# neuroskyStm.net
KiCad netlist of a schematic drawn in EAGLE
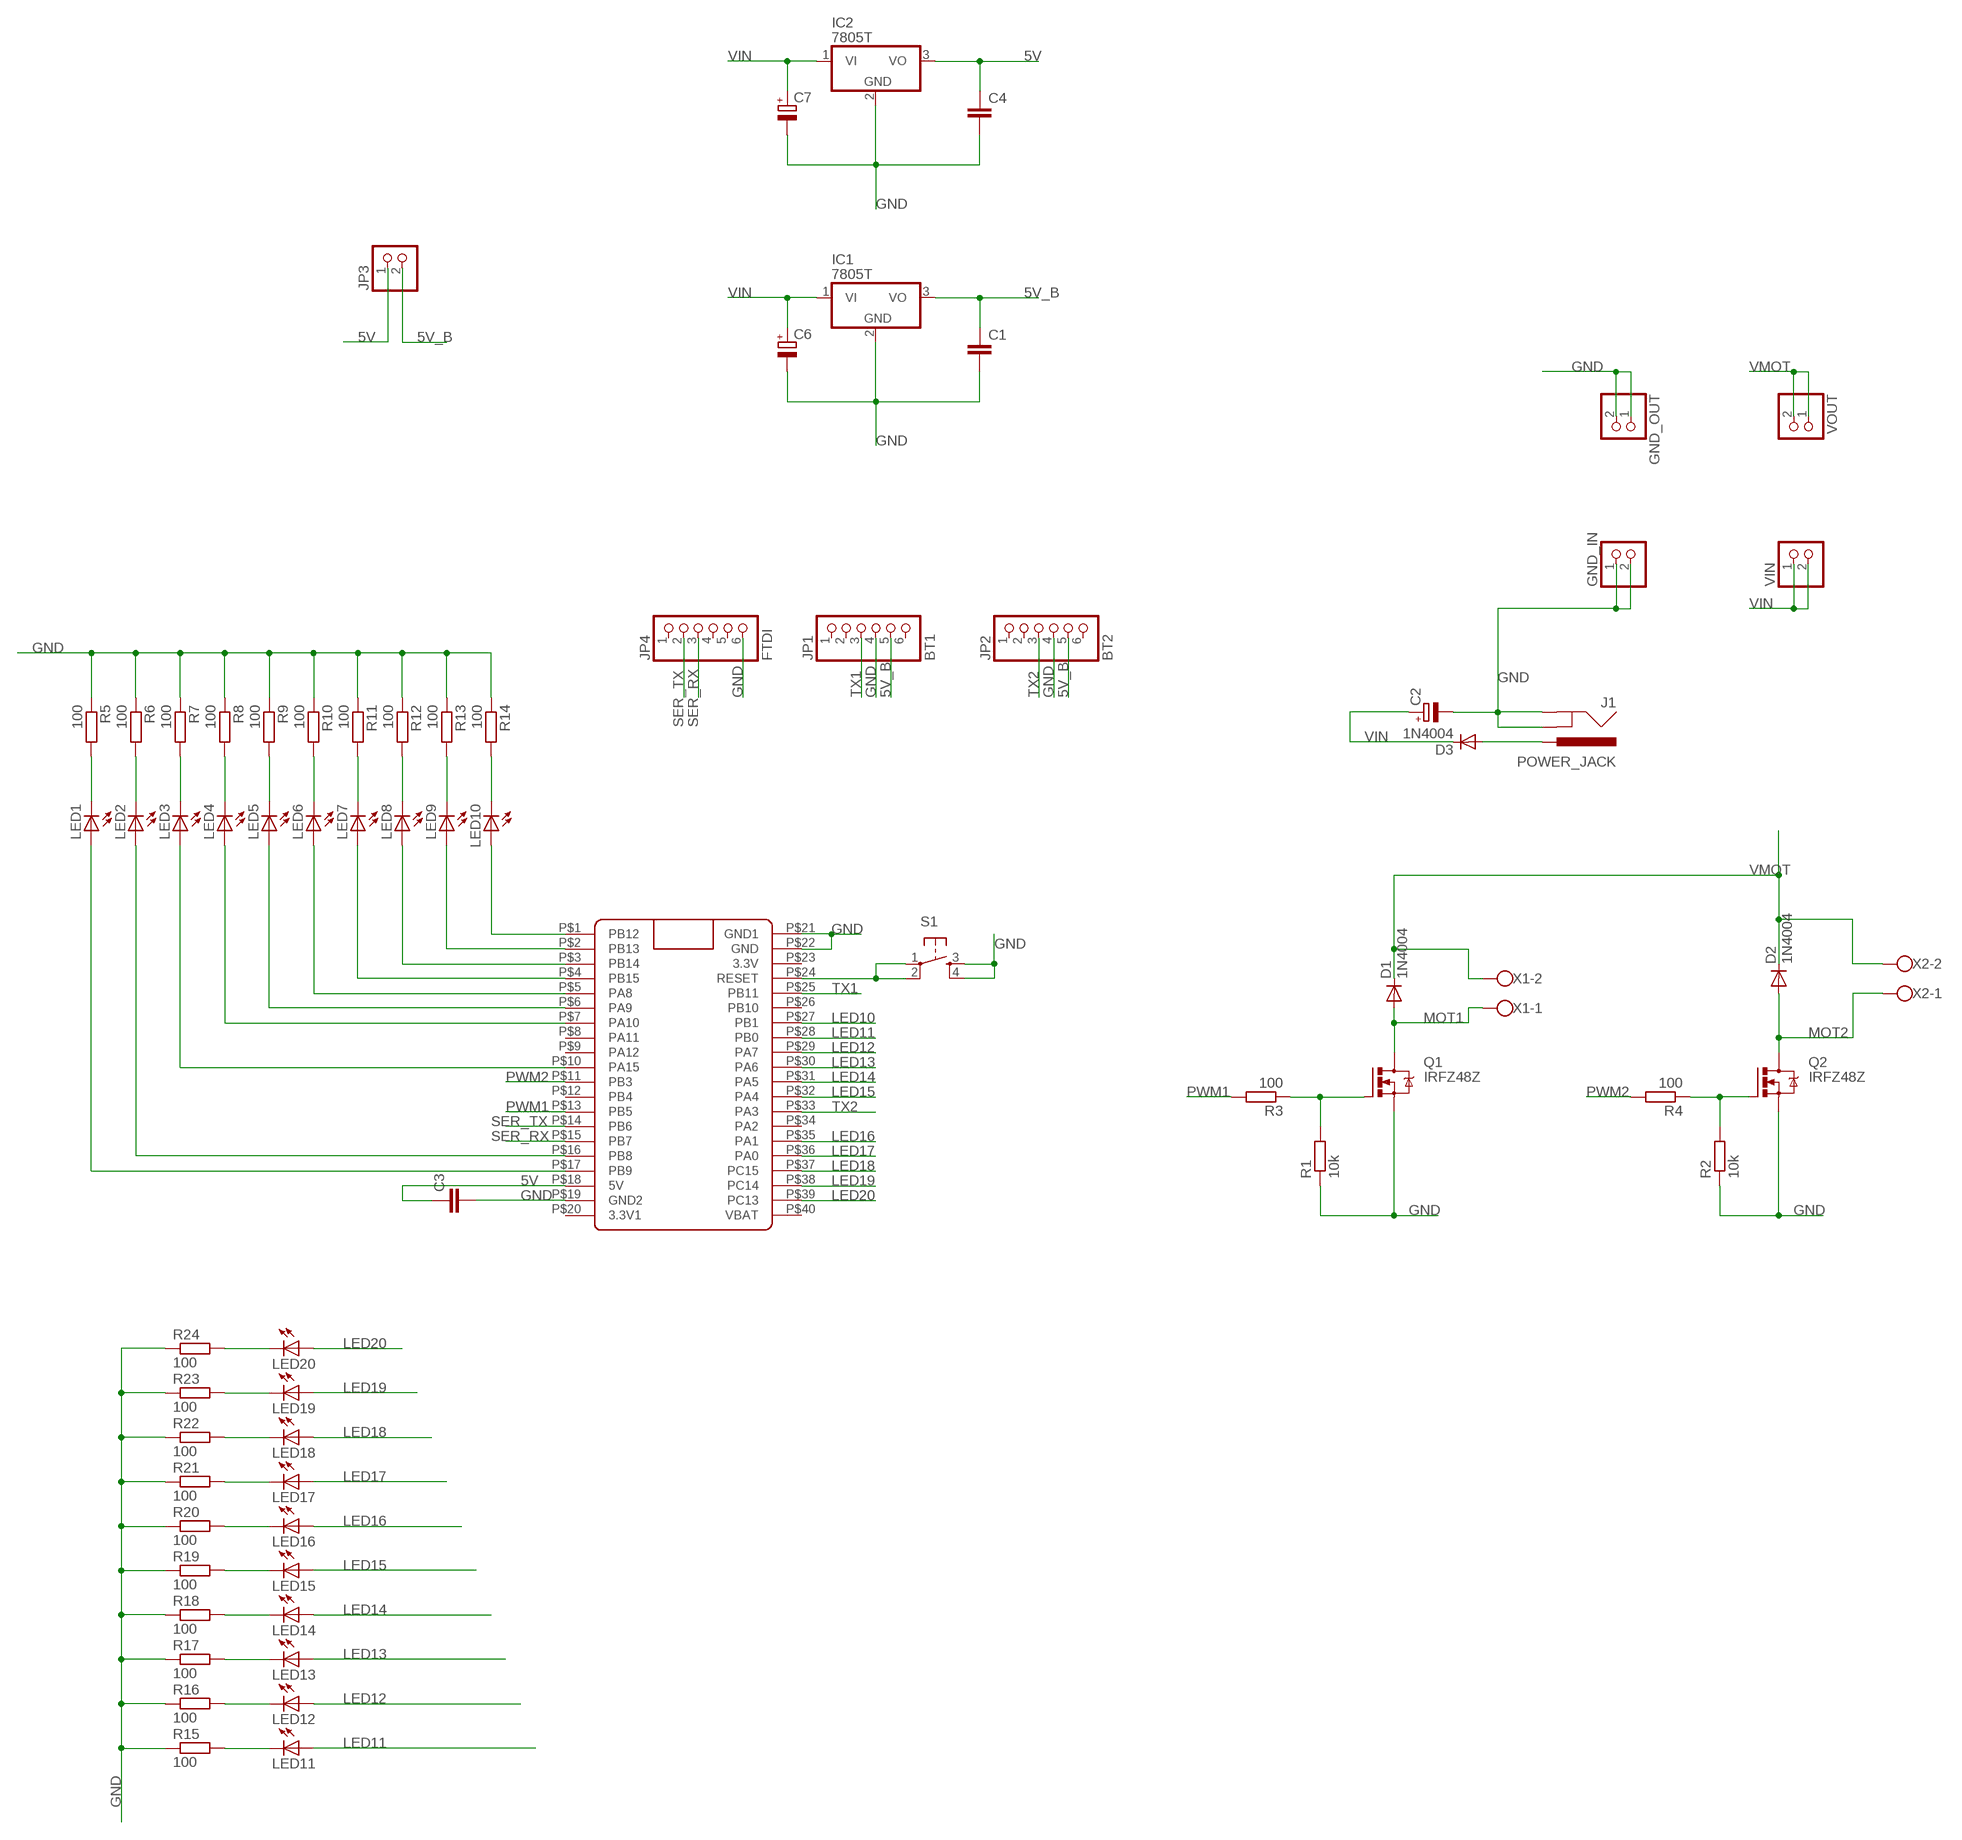
[diagram p0: schematic, sheet 1]

(export (version "E")
  (design (tool "Eeschema 10.0.6"))
  (components
    (comp (ref "C1")
      (value "C-EU050-035X075")
      (footprint "eagle-import:C050-035X075")
      (libsource (lib "eagle-import") (part "C-EU050-035X075"))
    )
    (comp (ref "C2")
      (value "CPOL-EUE3.5-8")
      (footprint "eagle-import:E3,5-8")
      (libsource (lib "eagle-import") (part "CPOL-EUE3.5-8"))
    )
    (comp (ref "C3")
      (value "C-EU050-035X075")
      (footprint "eagle-import:C050-035X075")
      (libsource (lib "eagle-import") (part "C-EU050-035X075"))
    )
    (comp (ref "C4")
      (value "C-EU050-035X075")
      (footprint "eagle-import:C050-035X075")
      (libsource (lib "eagle-import") (part "C-EU050-035X075"))
    )
    (comp (ref "C6")
      (value "CPOL-EUE3.5-8")
      (footprint "eagle-import:E3,5-8")
      (libsource (lib "eagle-import") (part "CPOL-EUE3.5-8"))
    )
    (comp (ref "C7")
      (value "CPOL-EUE3.5-8")
      (footprint "eagle-import:E3,5-8")
      (libsource (lib "eagle-import") (part "CPOL-EUE3.5-8"))
    )
    (comp (ref "D1")
      (value "1N4004")
      (footprint "eagle-import:DO41-10")
      (libsource (lib "eagle-import") (part "1N4004"))
    )
    (comp (ref "D2")
      (value "1N4004")
      (footprint "eagle-import:DO41-10")
      (libsource (lib "eagle-import") (part "1N4004"))
    )
    (comp (ref "D3")
      (value "1N4004")
      (footprint "eagle-import:DO41-10")
      (libsource (lib "eagle-import") (part "1N4004"))
    )
    (comp (ref "GND_IN")
      (value "PINHD-1X2")
      (footprint "eagle-import:1X02")
      (libsource (lib "eagle-import") (part "PINHD-1X2"))
    )
    (comp (ref "GND_OUT")
      (value "PINHD-1X2")
      (footprint "eagle-import:1X02")
      (libsource (lib "eagle-import") (part "PINHD-1X2"))
    )
    (comp (ref "IC1")
      (value "7805T")
      (footprint "eagle-import:TO220H")
      (libsource (lib "eagle-import") (part "78T05"))
    )
    (comp (ref "IC2")
      (value "7805T")
      (footprint "eagle-import:TO220H")
      (libsource (lib "eagle-import") (part "78T05"))
    )
    (comp (ref "J1")
      (value "POWER_JACK")
      (footprint "eagle-import:POWER_JACK_PTH")
      (libsource (lib "eagle-import") (part "POWER_JACK"))
    )
    (comp (ref "JP1")
      (value "BT1")
      (footprint "eagle-import:1X06")
      (libsource (lib "eagle-import") (part "PINHD-1X6"))
    )
    (comp (ref "JP2")
      (value "BT2")
      (footprint "eagle-import:1X06")
      (libsource (lib "eagle-import") (part "PINHD-1X6"))
    )
    (comp (ref "JP3")
      (value "PINHD-1X2")
      (footprint "eagle-import:1X02")
      (libsource (lib "eagle-import") (part "pinhead_325_PINHD-1X2"))
    )
    (comp (ref "JP4")
      (value "FTDI")
      (footprint "eagle-import:1X06")
      (libsource (lib "eagle-import") (part "PINHD-1X6"))
    )
    (comp (ref "LED1")
      (value "LED5MM")
      (footprint "eagle-import:LED5MM")
      (libsource (lib "eagle-import") (part "LED5MM"))
    )
    (comp (ref "LED2")
      (value "LED5MM")
      (footprint "eagle-import:LED5MM")
      (libsource (lib "eagle-import") (part "LED5MM"))
    )
    (comp (ref "LED3")
      (value "LED5MM")
      (footprint "eagle-import:LED5MM")
      (libsource (lib "eagle-import") (part "LED5MM"))
    )
    (comp (ref "LED4")
      (value "LED5MM")
      (footprint "eagle-import:LED5MM")
      (libsource (lib "eagle-import") (part "LED5MM"))
    )
    (comp (ref "LED5")
      (value "LED5MM")
      (footprint "eagle-import:LED5MM")
      (libsource (lib "eagle-import") (part "LED5MM"))
    )
    (comp (ref "LED6")
      (value "LED5MM")
      (footprint "eagle-import:LED5MM")
      (libsource (lib "eagle-import") (part "LED5MM"))
    )
    (comp (ref "LED7")
      (value "LED5MM")
      (footprint "eagle-import:LED5MM")
      (libsource (lib "eagle-import") (part "LED5MM"))
    )
    (comp (ref "LED8")
      (value "LED5MM")
      (footprint "eagle-import:LED5MM")
      (libsource (lib "eagle-import") (part "LED5MM"))
    )
    (comp (ref "LED9")
      (value "LED5MM")
      (footprint "eagle-import:LED5MM")
      (libsource (lib "eagle-import") (part "LED5MM"))
    )
    (comp (ref "LED10")
      (value "LED5MM")
      (footprint "eagle-import:LED5MM")
      (libsource (lib "eagle-import") (part "LED5MM"))
    )
    (comp (ref "LED11")
      (value "LED5MM")
      (footprint "eagle-import:LED5MM")
      (libsource (lib "eagle-import") (part "LED5MM"))
    )
    (comp (ref "LED12")
      (value "LED5MM")
      (footprint "eagle-import:LED5MM")
      (libsource (lib "eagle-import") (part "LED5MM"))
    )
    (comp (ref "LED13")
      (value "LED5MM")
      (footprint "eagle-import:LED5MM")
      (libsource (lib "eagle-import") (part "LED5MM"))
    )
    (comp (ref "LED14")
      (value "LED5MM")
      (footprint "eagle-import:LED5MM")
      (libsource (lib "eagle-import") (part "LED5MM"))
    )
    (comp (ref "LED15")
      (value "LED5MM")
      (footprint "eagle-import:LED5MM")
      (libsource (lib "eagle-import") (part "LED5MM"))
    )
    (comp (ref "LED16")
      (value "LED5MM")
      (footprint "eagle-import:LED5MM")
      (libsource (lib "eagle-import") (part "LED5MM"))
    )
    (comp (ref "LED17")
      (value "LED5MM")
      (footprint "eagle-import:LED5MM")
      (libsource (lib "eagle-import") (part "LED5MM"))
    )
    (comp (ref "LED18")
      (value "LED5MM")
      (footprint "eagle-import:LED5MM")
      (libsource (lib "eagle-import") (part "LED5MM"))
    )
    (comp (ref "LED19")
      (value "LED5MM")
      (footprint "eagle-import:LED5MM")
      (libsource (lib "eagle-import") (part "LED5MM"))
    )
    (comp (ref "LED20")
      (value "LED5MM")
      (footprint "eagle-import:LED5MM")
      (libsource (lib "eagle-import") (part "LED5MM"))
    )
    (comp (ref "Q1")
      (value "IRFZ48Z")
      (footprint "eagle-import:TO220BH")
      (libsource (lib "eagle-import") (part "IRFZ48Z"))
    )
    (comp (ref "Q2")
      (value "IRFZ48Z")
      (footprint "eagle-import:TO220BH")
      (libsource (lib "eagle-import") (part "IRFZ48Z"))
    )
    (comp (ref "R1")
      (value "10k")
      (footprint "eagle-import:0207_10")
      (libsource (lib "eagle-import") (part "R-EU_0207/10"))
    )
    (comp (ref "R2")
      (value "10k")
      (footprint "eagle-import:0207_10")
      (libsource (lib "eagle-import") (part "R-EU_0207/10"))
    )
    (comp (ref "R3")
      (value "100")
      (footprint "eagle-import:0207_10")
      (libsource (lib "eagle-import") (part "R-EU_0207/10"))
    )
    (comp (ref "R4")
      (value "100")
      (footprint "eagle-import:0207_10")
      (libsource (lib "eagle-import") (part "R-EU_0207/10"))
    )
    (comp (ref "R5")
      (value "100")
      (footprint "eagle-import:0207_10")
      (libsource (lib "eagle-import") (part "R-EU_0207/10"))
    )
    (comp (ref "R6")
      (value "100")
      (footprint "eagle-import:0207_10")
      (libsource (lib "eagle-import") (part "R-EU_0207/10"))
    )
    (comp (ref "R7")
      (value "100")
      (footprint "eagle-import:0207_10")
      (libsource (lib "eagle-import") (part "R-EU_0207/10"))
    )
    (comp (ref "R8")
      (value "100")
      (footprint "eagle-import:0207_10")
      (libsource (lib "eagle-import") (part "R-EU_0207/10"))
    )
    (comp (ref "R9")
      (value "100")
      (footprint "eagle-import:0207_10")
      (libsource (lib "eagle-import") (part "R-EU_0207/10"))
    )
    (comp (ref "R10")
      (value "100")
      (footprint "eagle-import:0207_10")
      (libsource (lib "eagle-import") (part "R-EU_0207/10"))
    )
    (comp (ref "R11")
      (value "100")
      (footprint "eagle-import:0207_10")
      (libsource (lib "eagle-import") (part "R-EU_0207/10"))
    )
    (comp (ref "R12")
      (value "100")
      (footprint "eagle-import:0207_10")
      (libsource (lib "eagle-import") (part "R-EU_0207/10"))
    )
    (comp (ref "R13")
      (value "100")
      (footprint "eagle-import:0207_10")
      (libsource (lib "eagle-import") (part "R-EU_0207/10"))
    )
    (comp (ref "R14")
      (value "100")
      (footprint "eagle-import:0207_10")
      (libsource (lib "eagle-import") (part "R-EU_0207/10"))
    )
    (comp (ref "R15")
      (value "100")
      (footprint "eagle-import:0207_10")
      (libsource (lib "eagle-import") (part "R-EU_0207/10"))
    )
    (comp (ref "R16")
      (value "100")
      (footprint "eagle-import:0207_10")
      (libsource (lib "eagle-import") (part "R-EU_0207/10"))
    )
    (comp (ref "R17")
      (value "100")
      (footprint "eagle-import:0207_10")
      (libsource (lib "eagle-import") (part "R-EU_0207/10"))
    )
    (comp (ref "R18")
      (value "100")
      (footprint "eagle-import:0207_10")
      (libsource (lib "eagle-import") (part "R-EU_0207/10"))
    )
    (comp (ref "R19")
      (value "100")
      (footprint "eagle-import:0207_10")
      (libsource (lib "eagle-import") (part "R-EU_0207/10"))
    )
    (comp (ref "R20")
      (value "100")
      (footprint "eagle-import:0207_10")
      (libsource (lib "eagle-import") (part "R-EU_0207/10"))
    )
    (comp (ref "R21")
      (value "100")
      (footprint "eagle-import:0207_10")
      (libsource (lib "eagle-import") (part "R-EU_0207/10"))
    )
    (comp (ref "R22")
      (value "100")
      (footprint "eagle-import:0207_10")
      (libsource (lib "eagle-import") (part "R-EU_0207/10"))
    )
    (comp (ref "R23")
      (value "100")
      (footprint "eagle-import:0207_10")
      (libsource (lib "eagle-import") (part "R-EU_0207/10"))
    )
    (comp (ref "R24")
      (value "100")
      (footprint "eagle-import:0207_10")
      (libsource (lib "eagle-import") (part "R-EU_0207/10"))
    )
    (comp (ref "S1")
      (value "TAC_SWITCHPTH")
      (footprint "eagle-import:TACTILE-PTH")
      (libsource (lib "eagle-import") (part "TAC_SWITCHPTH"))
    )
    (comp (ref "U$1")
      (value "BLUE_PILL")
      (footprint "eagle-import:BLUE_PILL")
      (libsource (lib "eagle-import") (part "BLUE_PILL"))
    )
    (comp (ref "VIN")
      (value "PINHD-1X2")
      (footprint "eagle-import:1X02")
      (libsource (lib "eagle-import") (part "PINHD-1X2"))
    )
    (comp (ref "VOUT")
      (value "PINHD-1X2")
      (footprint "eagle-import:1X02")
      (libsource (lib "eagle-import") (part "PINHD-1X2"))
    )
    (comp (ref "X1")
      (value "W237-102")
      (footprint "eagle-import:W237-102")
      (fields (field (name "MPN") "237-102"))
      (libsource (lib "eagle-import") (part "W237-102"))
    )
    (comp (ref "X2")
      (value "W237-102")
      (footprint "eagle-import:W237-102")
      (fields (field (name "MPN") "237-102"))
      (libsource (lib "eagle-import") (part "W237-102"))
    )
  )
  (nets
    (net (code "1") (name "/5V") (class "Default")
      (node (ref "C3") (pin "1") (pinfunction "1_1") (pintype "passive"))
      (node (ref "C4") (pin "1") (pinfunction "1_1") (pintype "passive"))
      (node (ref "IC2") (pin "3") (pinfunction "VO_3") (pintype "passive"))
      (node (ref "JP3") (pin "1") (pinfunction "1_1") (pintype "passive"))
      (node (ref "U$1") (pin "P$18") (pinfunction "5V_P$18") (pintype "bidirectional"))
    )
    (net (code "2") (name "/5V_B") (class "Default")
      (node (ref "C1") (pin "1") (pinfunction "1_1") (pintype "passive"))
      (node (ref "IC1") (pin "3") (pinfunction "VO_3") (pintype "passive"))
      (node (ref "JP1") (pin "5") (pinfunction "5_5") (pintype "passive"))
      (node (ref "JP2") (pin "5") (pinfunction "5_5") (pintype "passive"))
      (node (ref "JP3") (pin "2") (pinfunction "2_2") (pintype "passive"))
    )
    (net (code "3") (name "/GND") (class "Default")
      (node (ref "C1") (pin "2") (pinfunction "2_2") (pintype "passive"))
      (node (ref "C2") (pin "-") (pinfunction "-_-") (pintype "passive"))
      (node (ref "C3") (pin "2") (pinfunction "2_2") (pintype "passive"))
      (node (ref "C4") (pin "2") (pinfunction "2_2") (pintype "passive"))
      (node (ref "C6") (pin "-") (pinfunction "-_-") (pintype "passive"))
      (node (ref "C7") (pin "-") (pinfunction "-_-") (pintype "passive"))
      (node (ref "GND_IN") (pin "1") (pinfunction "1_1") (pintype "passive"))
      (node (ref "GND_IN") (pin "2") (pinfunction "2_2") (pintype "passive"))
      (node (ref "GND_OUT") (pin "1") (pinfunction "1_1") (pintype "passive"))
      (node (ref "GND_OUT") (pin "2") (pinfunction "2_2") (pintype "passive"))
      (node (ref "IC1") (pin "2") (pinfunction "GND_2") (pintype "passive"))
      (node (ref "IC2") (pin "2") (pinfunction "GND_2") (pintype "passive"))
      (node (ref "J1") (pin "GND") (pinfunction "GND_GND") (pintype "bidirectional"))
      (node (ref "J1") (pin "GNDBREAK") (pinfunction "GNDBREAK_GNDBREAK") (pintype "bidirectional"))
      (node (ref "JP1") (pin "4") (pinfunction "4_4") (pintype "passive"))
      (node (ref "JP2") (pin "4") (pinfunction "4_4") (pintype "passive"))
      (node (ref "JP4") (pin "6") (pinfunction "6_6") (pintype "passive"))
      (node (ref "Q1") (pin "S") (pinfunction "S_S") (pintype "passive"))
      (node (ref "Q2") (pin "S") (pinfunction "S_S") (pintype "passive"))
      (node (ref "R1") (pin "1") (pinfunction "1_1") (pintype "passive"))
      (node (ref "R10") (pin "1") (pinfunction "1_1") (pintype "passive"))
      (node (ref "R11") (pin "1") (pinfunction "1_1") (pintype "passive"))
      (node (ref "R12") (pin "1") (pinfunction "1_1") (pintype "passive"))
      (node (ref "R13") (pin "1") (pinfunction "1_1") (pintype "passive"))
      (node (ref "R14") (pin "1") (pinfunction "1_1") (pintype "passive"))
      (node (ref "R15") (pin "1") (pinfunction "1_1") (pintype "passive"))
      (node (ref "R16") (pin "1") (pinfunction "1_1") (pintype "passive"))
      (node (ref "R17") (pin "1") (pinfunction "1_1") (pintype "passive"))
      (node (ref "R18") (pin "1") (pinfunction "1_1") (pintype "passive"))
      (node (ref "R19") (pin "1") (pinfunction "1_1") (pintype "passive"))
      (node (ref "R2") (pin "1") (pinfunction "1_1") (pintype "passive"))
      (node (ref "R20") (pin "1") (pinfunction "1_1") (pintype "passive"))
      (node (ref "R21") (pin "1") (pinfunction "1_1") (pintype "passive"))
      (node (ref "R22") (pin "1") (pinfunction "1_1") (pintype "passive"))
      (node (ref "R23") (pin "1") (pinfunction "1_1") (pintype "passive"))
      (node (ref "R24") (pin "1") (pinfunction "1_1") (pintype "passive"))
      (node (ref "R5") (pin "1") (pinfunction "1_1") (pintype "passive"))
      (node (ref "R6") (pin "1") (pinfunction "1_1") (pintype "passive"))
      (node (ref "R7") (pin "1") (pinfunction "1_1") (pintype "passive"))
      (node (ref "R8") (pin "1") (pinfunction "1_1") (pintype "passive"))
      (node (ref "R9") (pin "1") (pinfunction "1_1") (pintype "passive"))
      (node (ref "S1") (pin "3") (pinfunction "3_3") (pintype "passive"))
      (node (ref "S1") (pin "4") (pinfunction "4_4") (pintype "passive"))
      (node (ref "U$1") (pin "P$19") (pinfunction "GND2_P$19") (pintype "bidirectional"))
      (node (ref "U$1") (pin "P$21") (pinfunction "GND1_P$21") (pintype "power_in"))
      (node (ref "U$1") (pin "P$22") (pinfunction "GND_P$22") (pintype "bidirectional"))
    )
    (net (code "4") (name "/LED10") (class "Default")
      (node (ref "U$1") (pin "P$27") (pinfunction "PB1_P$27") (pintype "bidirectional"))
    )
    (net (code "5") (name "/LED11") (class "Default")
      (node (ref "LED11") (pin "A") (pinfunction "A_A") (pintype "passive"))
      (node (ref "U$1") (pin "P$28") (pinfunction "PB0_P$28") (pintype "bidirectional"))
    )
    (net (code "6") (name "/LED12") (class "Default")
      (node (ref "LED12") (pin "A") (pinfunction "A_A") (pintype "passive"))
      (node (ref "U$1") (pin "P$29") (pinfunction "PA7_P$29") (pintype "bidirectional"))
    )
    (net (code "7") (name "/LED13") (class "Default")
      (node (ref "LED13") (pin "A") (pinfunction "A_A") (pintype "passive"))
      (node (ref "U$1") (pin "P$30") (pinfunction "PA6_P$30") (pintype "bidirectional"))
    )
    (net (code "8") (name "/LED14") (class "Default")
      (node (ref "LED14") (pin "A") (pinfunction "A_A") (pintype "passive"))
      (node (ref "U$1") (pin "P$31") (pinfunction "PA5_P$31") (pintype "bidirectional"))
    )
    (net (code "9") (name "/LED15") (class "Default")
      (node (ref "LED15") (pin "A") (pinfunction "A_A") (pintype "passive"))
      (node (ref "U$1") (pin "P$32") (pinfunction "PA4_P$32") (pintype "bidirectional"))
    )
    (net (code "10") (name "/LED16") (class "Default")
      (node (ref "LED16") (pin "A") (pinfunction "A_A") (pintype "passive"))
      (node (ref "U$1") (pin "P$35") (pinfunction "PA1_P$35") (pintype "bidirectional"))
    )
    (net (code "11") (name "/LED17") (class "Default")
      (node (ref "LED17") (pin "A") (pinfunction "A_A") (pintype "passive"))
      (node (ref "U$1") (pin "P$36") (pinfunction "PA0_P$36") (pintype "bidirectional"))
    )
    (net (code "12") (name "/LED18") (class "Default")
      (node (ref "LED18") (pin "A") (pinfunction "A_A") (pintype "passive"))
      (node (ref "U$1") (pin "P$37") (pinfunction "PC15_P$37") (pintype "bidirectional"))
    )
    (net (code "13") (name "/LED19") (class "Default")
      (node (ref "LED19") (pin "A") (pinfunction "A_A") (pintype "passive"))
      (node (ref "U$1") (pin "P$38") (pinfunction "PC14_P$38") (pintype "bidirectional"))
    )
    (net (code "14") (name "/LED20") (class "Default")
      (node (ref "LED20") (pin "A") (pinfunction "A_A") (pintype "passive"))
      (node (ref "U$1") (pin "P$39") (pinfunction "PC13_P$39") (pintype "bidirectional"))
    )
    (net (code "15") (name "/MOT1") (class "Default")
      (node (ref "D1") (pin "A") (pinfunction "A_A") (pintype "passive"))
      (node (ref "Q1") (pin "D") (pinfunction "D_D") (pintype "passive"))
      (node (ref "X1") (pin "1") (pinfunction "KL_1") (pintype "passive"))
    )
    (net (code "16") (name "/MOT2") (class "Default")
      (node (ref "D2") (pin "A") (pinfunction "A_A") (pintype "passive"))
      (node (ref "Q2") (pin "D") (pinfunction "D_D") (pintype "passive"))
      (node (ref "X2") (pin "1") (pinfunction "KL_1") (pintype "passive"))
    )
    (net (code "17") (name "/PWM1") (class "Default")
      (node (ref "R3") (pin "2") (pinfunction "2_2") (pintype "passive"))
      (node (ref "U$1") (pin "P$13") (pinfunction "PB5_P$13") (pintype "bidirectional"))
    )
    (net (code "18") (name "/PWM2") (class "Default")
      (node (ref "R4") (pin "2") (pinfunction "2_2") (pintype "passive"))
      (node (ref "U$1") (pin "P$11") (pinfunction "PB3_P$11") (pintype "bidirectional"))
    )
    (net (code "19") (name "/SER_RX") (class "Default")
      (node (ref "JP4") (pin "3") (pinfunction "3_3") (pintype "passive"))
      (node (ref "U$1") (pin "P$15") (pinfunction "PB7_P$15") (pintype "bidirectional"))
    )
    (net (code "20") (name "/SER_TX") (class "Default")
      (node (ref "JP4") (pin "2") (pinfunction "2_2") (pintype "passive"))
      (node (ref "U$1") (pin "P$14") (pinfunction "PB6_P$14") (pintype "bidirectional"))
    )
    (net (code "21") (name "/TX1") (class "Default")
      (node (ref "JP1") (pin "3") (pinfunction "3_3") (pintype "passive"))
      (node (ref "U$1") (pin "P$25") (pinfunction "PB11_P$25") (pintype "bidirectional"))
    )
    (net (code "22") (name "/TX2") (class "Default")
      (node (ref "JP2") (pin "3") (pinfunction "3_3") (pintype "passive"))
      (node (ref "U$1") (pin "P$33") (pinfunction "PA3_P$33") (pintype "bidirectional"))
    )
    (net (code "23") (name "/VIN") (class "Default")
      (node (ref "C2") (pin "+") (pinfunction "+_+") (pintype "passive"))
      (node (ref "C6") (pin "+") (pinfunction "+_+") (pintype "passive"))
      (node (ref "C7") (pin "+") (pinfunction "+_+") (pintype "passive"))
      (node (ref "D3") (pin "C") (pinfunction "C_C") (pintype "passive"))
      (node (ref "IC1") (pin "1") (pinfunction "VI_1") (pintype "input"))
      (node (ref "IC2") (pin "1") (pinfunction "VI_1") (pintype "input"))
      (node (ref "VIN") (pin "1") (pinfunction "1_1") (pintype "passive"))
      (node (ref "VIN") (pin "2") (pinfunction "2_2") (pintype "passive"))
    )
    (net (code "24") (name "/VMOT") (class "Default")
      (node (ref "D1") (pin "C") (pinfunction "C_C") (pintype "passive"))
      (node (ref "D2") (pin "C") (pinfunction "C_C") (pintype "passive"))
      (node (ref "VOUT") (pin "1") (pinfunction "1_1") (pintype "passive"))
      (node (ref "VOUT") (pin "2") (pinfunction "2_2") (pintype "passive"))
      (node (ref "X1") (pin "2") (pinfunction "KL_2") (pintype "passive"))
      (node (ref "X2") (pin "2") (pinfunction "KL_2") (pintype "passive"))
    )
    (net (code "25") (name "Net-(D3-PadA)") (class "Default")
      (node (ref "D3") (pin "A") (pinfunction "A_A") (pintype "passive"))
      (node (ref "J1") (pin "PWR") (pinfunction "PWR_PWR") (pintype "bidirectional"))
    )
    (net (code "26") (name "Net-(LED1-C)") (class "Default")
      (node (ref "LED1") (pin "K") (pinfunction "C_K") (pintype "passive"))
      (node (ref "R5") (pin "2") (pinfunction "2_2") (pintype "passive"))
    )
    (net (code "27") (name "Net-(LED2-C)") (class "Default")
      (node (ref "LED2") (pin "K") (pinfunction "C_K") (pintype "passive"))
      (node (ref "R6") (pin "2") (pinfunction "2_2") (pintype "passive"))
    )
    (net (code "28") (name "Net-(LED3-C)") (class "Default")
      (node (ref "LED3") (pin "K") (pinfunction "C_K") (pintype "passive"))
      (node (ref "R7") (pin "2") (pinfunction "2_2") (pintype "passive"))
    )
    (net (code "29") (name "Net-(LED4-C)") (class "Default")
      (node (ref "LED4") (pin "K") (pinfunction "C_K") (pintype "passive"))
      (node (ref "R8") (pin "2") (pinfunction "2_2") (pintype "passive"))
    )
    (net (code "30") (name "Net-(LED5-C)") (class "Default")
      (node (ref "LED5") (pin "K") (pinfunction "C_K") (pintype "passive"))
      (node (ref "R9") (pin "2") (pinfunction "2_2") (pintype "passive"))
    )
    (net (code "31") (name "Net-(LED6-C)") (class "Default")
      (node (ref "LED6") (pin "K") (pinfunction "C_K") (pintype "passive"))
      (node (ref "R10") (pin "2") (pinfunction "2_2") (pintype "passive"))
    )
    (net (code "32") (name "Net-(LED7-C)") (class "Default")
      (node (ref "LED7") (pin "K") (pinfunction "C_K") (pintype "passive"))
      (node (ref "R11") (pin "2") (pinfunction "2_2") (pintype "passive"))
    )
    (net (code "33") (name "Net-(LED8-C)") (class "Default")
      (node (ref "LED8") (pin "K") (pinfunction "C_K") (pintype "passive"))
      (node (ref "R12") (pin "2") (pinfunction "2_2") (pintype "passive"))
    )
    (net (code "34") (name "Net-(LED9-C)") (class "Default")
      (node (ref "LED9") (pin "K") (pinfunction "C_K") (pintype "passive"))
      (node (ref "R13") (pin "2") (pinfunction "2_2") (pintype "passive"))
    )
    (net (code "35") (name "Net-(LED10-C)") (class "Default")
      (node (ref "LED10") (pin "K") (pinfunction "C_K") (pintype "passive"))
      (node (ref "R14") (pin "2") (pinfunction "2_2") (pintype "passive"))
    )
    (net (code "36") (name "Net-(LED11-C)") (class "Default")
      (node (ref "LED11") (pin "K") (pinfunction "C_K") (pintype "passive"))
      (node (ref "R15") (pin "2") (pinfunction "2_2") (pintype "passive"))
    )
    (net (code "37") (name "Net-(LED12-C)") (class "Default")
      (node (ref "LED12") (pin "K") (pinfunction "C_K") (pintype "passive"))
      (node (ref "R16") (pin "2") (pinfunction "2_2") (pintype "passive"))
    )
    (net (code "38") (name "Net-(LED13-C)") (class "Default")
      (node (ref "LED13") (pin "K") (pinfunction "C_K") (pintype "passive"))
      (node (ref "R17") (pin "2") (pinfunction "2_2") (pintype "passive"))
    )
    (net (code "39") (name "Net-(LED14-C)") (class "Default")
      (node (ref "LED14") (pin "K") (pinfunction "C_K") (pintype "passive"))
      (node (ref "R18") (pin "2") (pinfunction "2_2") (pintype "passive"))
    )
    (net (code "40") (name "Net-(LED15-C)") (class "Default")
      (node (ref "LED15") (pin "K") (pinfunction "C_K") (pintype "passive"))
      (node (ref "R19") (pin "2") (pinfunction "2_2") (pintype "passive"))
    )
    (net (code "41") (name "Net-(LED16-C)") (class "Default")
      (node (ref "LED16") (pin "K") (pinfunction "C_K") (pintype "passive"))
      (node (ref "R20") (pin "2") (pinfunction "2_2") (pintype "passive"))
    )
    (net (code "42") (name "Net-(LED17-C)") (class "Default")
      (node (ref "LED17") (pin "K") (pinfunction "C_K") (pintype "passive"))
      (node (ref "R21") (pin "2") (pinfunction "2_2") (pintype "passive"))
    )
    (net (code "43") (name "Net-(LED18-C)") (class "Default")
      (node (ref "LED18") (pin "K") (pinfunction "C_K") (pintype "passive"))
      (node (ref "R22") (pin "2") (pinfunction "2_2") (pintype "passive"))
    )
    (net (code "44") (name "Net-(LED19-C)") (class "Default")
      (node (ref "LED19") (pin "K") (pinfunction "C_K") (pintype "passive"))
      (node (ref "R23") (pin "2") (pinfunction "2_2") (pintype "passive"))
    )
    (net (code "45") (name "Net-(LED20-C)") (class "Default")
      (node (ref "LED20") (pin "K") (pinfunction "C_K") (pintype "passive"))
      (node (ref "R24") (pin "2") (pinfunction "2_2") (pintype "passive"))
    )
    (net (code "46") (name "Net-(Q1-PadG)") (class "Default")
      (node (ref "Q1") (pin "G") (pinfunction "G_G") (pintype "passive"))
      (node (ref "R1") (pin "2") (pinfunction "2_2") (pintype "passive"))
      (node (ref "R3") (pin "1") (pinfunction "1_1") (pintype "passive"))
    )
    (net (code "47") (name "Net-(Q2-PadG)") (class "Default")
      (node (ref "Q2") (pin "G") (pinfunction "G_G") (pintype "passive"))
      (node (ref "R2") (pin "2") (pinfunction "2_2") (pintype "passive"))
      (node (ref "R4") (pin "1") (pinfunction "1_1") (pintype "passive"))
    )
    (net (code "48") (name "Net-(U$1-PA8)") (class "Default")
      (node (ref "LED6") (pin "A") (pinfunction "A_A") (pintype "passive"))
      (node (ref "U$1") (pin "P$5") (pinfunction "PA8_P$5") (pintype "bidirectional"))
    )
    (net (code "49") (name "Net-(U$1-PA9)") (class "Default")
      (node (ref "LED5") (pin "A") (pinfunction "A_A") (pintype "passive"))
      (node (ref "U$1") (pin "P$6") (pinfunction "PA9_P$6") (pintype "bidirectional"))
    )
    (net (code "50") (name "Net-(U$1-PA10)") (class "Default")
      (node (ref "LED4") (pin "A") (pinfunction "A_A") (pintype "passive"))
      (node (ref "U$1") (pin "P$7") (pinfunction "PA10_P$7") (pintype "bidirectional"))
    )
    (net (code "51") (name "Net-(U$1-PA15)") (class "Default")
      (node (ref "LED3") (pin "A") (pinfunction "A_A") (pintype "passive"))
      (node (ref "U$1") (pin "P$10") (pinfunction "PA15_P$10") (pintype "bidirectional"))
    )
    (net (code "52") (name "Net-(U$1-PB8)") (class "Default")
      (node (ref "LED2") (pin "A") (pinfunction "A_A") (pintype "passive"))
      (node (ref "U$1") (pin "P$16") (pinfunction "PB8_P$16") (pintype "bidirectional"))
    )
    (net (code "53") (name "Net-(U$1-PB9)") (class "Default")
      (node (ref "LED1") (pin "A") (pinfunction "A_A") (pintype "passive"))
      (node (ref "U$1") (pin "P$17") (pinfunction "PB9_P$17") (pintype "bidirectional"))
    )
    (net (code "54") (name "Net-(U$1-PB12)") (class "Default")
      (node (ref "LED10") (pin "A") (pinfunction "A_A") (pintype "passive"))
      (node (ref "U$1") (pin "P$1") (pinfunction "PB12_P$1") (pintype "bidirectional"))
    )
    (net (code "55") (name "Net-(U$1-PB13)") (class "Default")
      (node (ref "LED9") (pin "A") (pinfunction "A_A") (pintype "passive"))
      (node (ref "U$1") (pin "P$2") (pinfunction "PB13_P$2") (pintype "bidirectional"))
    )
    (net (code "56") (name "Net-(U$1-PB14)") (class "Default")
      (node (ref "LED8") (pin "A") (pinfunction "A_A") (pintype "passive"))
      (node (ref "U$1") (pin "P$3") (pinfunction "PB14_P$3") (pintype "bidirectional"))
    )
    (net (code "57") (name "Net-(U$1-PB15)") (class "Default")
      (node (ref "LED7") (pin "A") (pinfunction "A_A") (pintype "passive"))
      (node (ref "U$1") (pin "P$4") (pinfunction "PB15_P$4") (pintype "bidirectional"))
    )
    (net (code "58") (name "Net-(U$1-RESET)") (class "Default")
      (node (ref "S1") (pin "1") (pinfunction "1_1") (pintype "passive"))
      (node (ref "S1") (pin "2") (pinfunction "2_2") (pintype "passive"))
      (node (ref "U$1") (pin "P$24") (pinfunction "RESET_P$24") (pintype "bidirectional"))
    )
    (net (code "59") (name "unconnected-(JP1-Pad1)") (class "Default")
      (node (ref "JP1") (pin "1") (pinfunction "1_1") (pintype "passive"))
    )
    (net (code "60") (name "unconnected-(JP1-Pad2)") (class "Default")
      (node (ref "JP1") (pin "2") (pinfunction "2_2") (pintype "passive"))
    )
    (net (code "61") (name "unconnected-(JP1-Pad6)") (class "Default")
      (node (ref "JP1") (pin "6") (pinfunction "6_6") (pintype "passive"))
    )
    (net (code "62") (name "unconnected-(JP2-Pad1)") (class "Default")
      (node (ref "JP2") (pin "1") (pinfunction "1_1") (pintype "passive"))
    )
    (net (code "63") (name "unconnected-(JP2-Pad2)") (class "Default")
      (node (ref "JP2") (pin "2") (pinfunction "2_2") (pintype "passive"))
    )
    (net (code "64") (name "unconnected-(JP2-Pad6)") (class "Default")
      (node (ref "JP2") (pin "6") (pinfunction "6_6") (pintype "passive"))
    )
    (net (code "65") (name "unconnected-(JP4-Pad1)") (class "Default")
      (node (ref "JP4") (pin "1") (pinfunction "1_1") (pintype "passive"))
    )
    (net (code "66") (name "unconnected-(JP4-Pad4)") (class "Default")
      (node (ref "JP4") (pin "4") (pinfunction "4_4") (pintype "passive"))
    )
    (net (code "67") (name "unconnected-(JP4-Pad5)") (class "Default")
      (node (ref "JP4") (pin "5") (pinfunction "5_5") (pintype "passive"))
    )
    (net (code "68") (name "unconnected-(U$1-3.3V-PadP$23)") (class "Default")
      (node (ref "U$1") (pin "P$23") (pinfunction "3.3V_P$23") (pintype "bidirectional"))
    )
    (net (code "69") (name "unconnected-(U$1-3.3V1-PadP$20)") (class "Default")
      (node (ref "U$1") (pin "P$20") (pinfunction "3.3V1_P$20") (pintype "bidirectional"))
    )
    (net (code "70") (name "unconnected-(U$1-PA2-PadP$34)") (class "Default")
      (node (ref "U$1") (pin "P$34") (pinfunction "PA2_P$34") (pintype "bidirectional"))
    )
    (net (code "71") (name "unconnected-(U$1-PA11-PadP$8)") (class "Default")
      (node (ref "U$1") (pin "P$8") (pinfunction "PA11_P$8") (pintype "bidirectional"))
    )
    (net (code "72") (name "unconnected-(U$1-PA12-PadP$9)") (class "Default")
      (node (ref "U$1") (pin "P$9") (pinfunction "PA12_P$9") (pintype "bidirectional"))
    )
    (net (code "73") (name "unconnected-(U$1-PB4-PadP$12)") (class "Default")
      (node (ref "U$1") (pin "P$12") (pinfunction "PB4_P$12") (pintype "bidirectional"))
    )
    (net (code "74") (name "unconnected-(U$1-PB10-PadP$26)") (class "Default")
      (node (ref "U$1") (pin "P$26") (pinfunction "PB10_P$26") (pintype "bidirectional"))
    )
    (net (code "75") (name "unconnected-(U$1-VBAT-PadP$40)") (class "Default")
      (node (ref "U$1") (pin "P$40") (pinfunction "VBAT_P$40") (pintype "bidirectional"))
    )
  )
)
